# Out1.net
KiCad netlist of a schematic drawn in Altium Designer
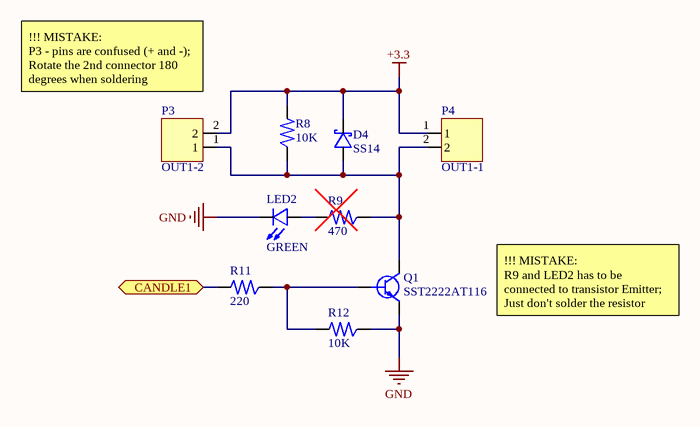
[diagram p0: Out1.SchDoc]

(export (version "E")
  (design (tool "Eeschema 10.0.6"))
  (components
    (comp (ref "D4")
      (value "SS14")
      (footprint "SMT_DIODE_SCHTKY_VISHAI")
      (description "SMT Diode Schottky Vishay DO-214AC SS14-M3/5AT IF=1A VR=40 V FV=0.5VG")
      (libsource (lib "SMT_DIODE_SCHTKY_VISHAI") (part "SMT_DIODE_SCHTKY_VISHAI"))
    )
    (comp (ref "LED2")
      (value "GREEN")
      (footprint "SMT_LED_0805(2012)_WURTH")
      (description "LED 0805(2012) 20mA 2V 150080YS75000 by Wurth Elektronik")
      (libsource (lib "SMT_LED_0805(2012)_WURTH") (part "SMT_LED_0805(2012)_WURTH"))
    )
    (comp (ref "P3")
      (value "OUT1-2")
      (footprint "THT_CON_WAFER_2P_NEL_2217S-02-WH2")
      (description "Connector Wafer NELTRON 2-Pins Pitch-2.54mm 250V/3A 2217S-02-WH2")
      (libsource (lib "") (part "THT_CON_WAFER_2P_NEL_2217S-02-WH2_1"))
    )
    (comp (ref "P4")
      (value "OUT1-1")
      (footprint "THT_CON_WAFER_2P_NEL_2217S-02-WH2")
      (description "Connector Wafer NELTRON 2-Pins Pitch-2.54mm 250V/3A 2217S-02-WH2")
      (libsource (lib "THT_CON_WAFER_2P_NEL_2217S-02-WH2") (part "THT_CON_WAFER_2P_NEL_2217S-02-WH2"))
    )
    (comp (ref "Q1")
      (value "SST2222AT116")
      (footprint "SMT_TRANS_SST2222AT116_SOT23")
      (description "Transistor NPN SST2222AT116 SOT23 700mA 40V")
      (libsource (lib "SMT_TRANS_SST2222AT116_SOT23") (part "SMT_TRANS_SST2222AT116_SOT23"))
    )
    (comp (ref "R8")
      (value "10K")
      (footprint "SMT_RES_0805(2012)")
      (description "0805(2012) Resistor 1/4-1/8W 150V 2A")
      (libsource (lib "SMT_RES_0805(2012)") (part "SMT_RES_0805(2012)"))
    )
    (comp (ref "R9")
      (value "470")
      (footprint "SMT_RES_0805(2012)")
      (description "0805(2012) Resistor 1/4-1/8W 150V 2A")
      (libsource (lib "SMT_RES_0805(2012)") (part "SMT_RES_0805(2012)"))
    )
    (comp (ref "R11")
      (value "220")
      (footprint "SMT_RES_0805(2012)")
      (description "0805(2012) Resistor 1/4-1/8W 150V 2A")
      (libsource (lib "SMT_RES_0805(2012)") (part "SMT_RES_0805(2012)"))
    )
    (comp (ref "R12")
      (value "10K")
      (footprint "SMT_RES_0805(2012)")
      (description "0805(2012) Resistor 1/4-1/8W 150V 2A")
      (libsource (lib "SMT_RES_0805(2012)") (part "SMT_RES_0805(2012)"))
    )
  )
  (nets
    (net (code "1") (name "+3.3") (class "Default")
      (node (ref "D4") (pin "2") (pinfunction "2_2") (pintype "passive"))
      (node (ref "P3") (pin "2") (pinfunction "2_2") (pintype "passive"))
      (node (ref "P4") (pin "1") (pinfunction "1_1") (pintype "passive"))
      (node (ref "R8") (pin "1") (pinfunction "1_1") (pintype "passive"))
    )
    (net (code "2") (name "/CANDLE1") (class "Default")
      (node (ref "R11") (pin "1") (pinfunction "1_1") (pintype "passive"))
    )
    (net (code "3") (name "GND") (class "Default")
      (node (ref "LED2") (pin "1") (pinfunction "1_1") (pintype "passive"))
      (node (ref "Q1") (pin "1") (pinfunction "E_1") (pintype "passive"))
      (node (ref "R12") (pin "2") (pinfunction "2_2") (pintype "passive"))
    )
    (net (code "4") (name "Net-(LED2-Pad2)") (class "Default")
      (node (ref "LED2") (pin "2") (pinfunction "2_2") (pintype "passive"))
      (node (ref "R9") (pin "1") (pinfunction "1_1") (pintype "passive"))
    )
    (net (code "5") (name "Net-(Q1-B)") (class "Default")
      (node (ref "Q1") (pin "2") (pinfunction "B_2") (pintype "passive"))
      (node (ref "R11") (pin "2") (pinfunction "2_2") (pintype "passive"))
      (node (ref "R12") (pin "1") (pinfunction "1_1") (pintype "passive"))
    )
    (net (code "6") (name "Net-(Q1-C)") (class "Default")
      (node (ref "D4") (pin "1") (pinfunction "1_1") (pintype "passive"))
      (node (ref "P3") (pin "1") (pinfunction "1_1") (pintype "passive"))
      (node (ref "P4") (pin "2") (pinfunction "2_2") (pintype "passive"))
      (node (ref "Q1") (pin "3") (pinfunction "C_3") (pintype "passive"))
      (node (ref "R8") (pin "2") (pinfunction "2_2") (pintype "passive"))
      (node (ref "R9") (pin "2") (pinfunction "2_2") (pintype "passive"))
    )
  )
)
